# MCU.net
KiCad netlist of a schematic drawn in Altium Designer
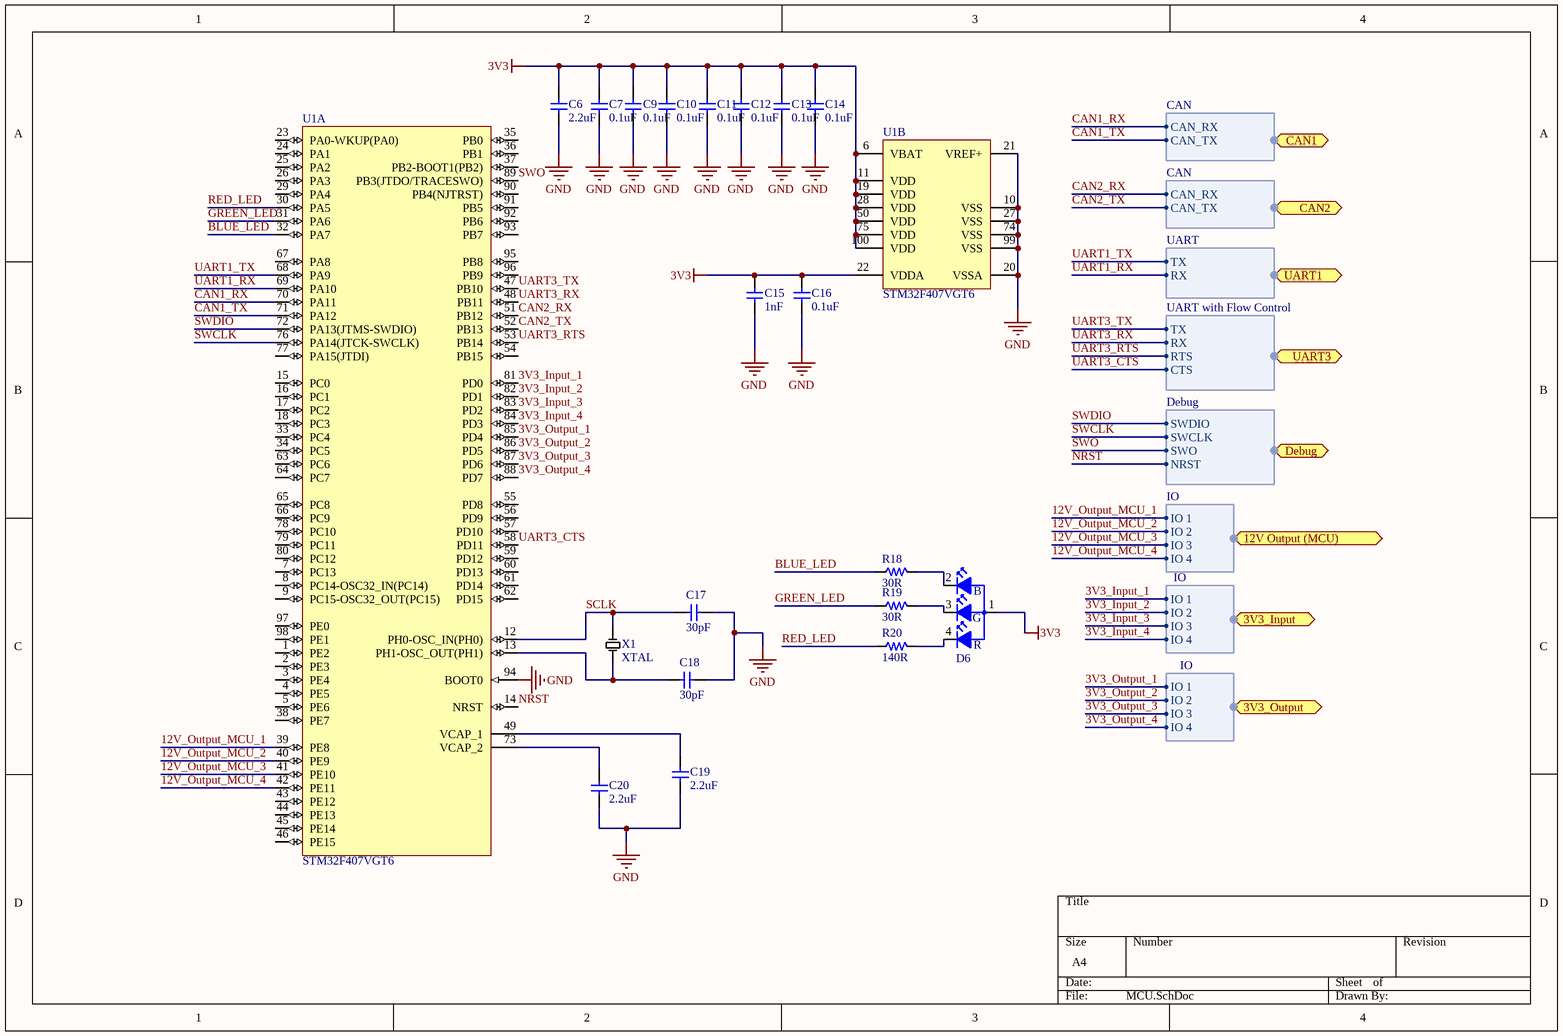
[diagram p0: MCU.SchDoc]

(export (version "E")
  (design (tool "Eeschema 10.0.6"))
  (components
    (comp (ref "C6")
      (value "2.2uF")
      (footprint "PCB_GENERIC_SMD_0603")
      (description "CAP CER 0603 2.2uF 16V X5R 20%")
      (fields (field (name "TOLERANCE") "20%") (field (name "VOLTAGE") "16V"))
      (libsource (lib "CAP-0603") (part "C060-002U2-00"))
    )
    (comp (ref "C7")
      (value "0.1uF")
      (footprint "PCB_GENERIC_SMD_0603")
      (description "CAP CER 0603 0.1uF 16V X5R 20%")
      (fields (field (name "TOLERANCE") "20%") (field (name "VOLTAGE") "16V"))
      (libsource (lib "CAP-0603") (part "C060-000U1-00"))
    )
    (comp (ref "C9")
      (value "0.1uF")
      (footprint "PCB_GENERIC_SMD_0603")
      (description "CAP CER 0603 0.1uF 16V X5R 20%")
      (fields (field (name "TOLERANCE") "20%") (field (name "VOLTAGE") "16V"))
      (libsource (lib "CAP-0603") (part "C060-000U1-00"))
    )
    (comp (ref "C10")
      (value "0.1uF")
      (footprint "PCB_GENERIC_SMD_0603")
      (description "CAP CER 0603 0.1uF 16V X5R 20%")
      (fields (field (name "TOLERANCE") "20%") (field (name "VOLTAGE") "16V"))
      (libsource (lib "CAP-0603") (part "C060-000U1-00"))
    )
    (comp (ref "C11")
      (value "0.1uF")
      (footprint "PCB_GENERIC_SMD_0603")
      (description "CAP CER 0603 0.1uF 16V X5R 20%")
      (fields (field (name "TOLERANCE") "20%") (field (name "VOLTAGE") "16V"))
      (libsource (lib "CAP-0603") (part "C060-000U1-00"))
    )
    (comp (ref "C12")
      (value "0.1uF")
      (footprint "PCB_GENERIC_SMD_0603")
      (description "CAP CER 0603 0.1uF 16V X5R 20%")
      (fields (field (name "TOLERANCE") "20%") (field (name "VOLTAGE") "16V"))
      (libsource (lib "CAP-0603") (part "C060-000U1-00"))
    )
    (comp (ref "C13")
      (value "0.1uF")
      (footprint "PCB_GENERIC_SMD_0603")
      (description "CAP CER 0603 0.1uF 16V X5R 20%")
      (fields (field (name "TOLERANCE") "20%") (field (name "VOLTAGE") "16V"))
      (libsource (lib "CAP-0603") (part "C060-000U1-00"))
    )
    (comp (ref "C14")
      (value "0.1uF")
      (footprint "PCB_GENERIC_SMD_0603")
      (description "CAP CER 0603 0.1uF 16V X5R 20%")
      (fields (field (name "TOLERANCE") "20%") (field (name "VOLTAGE") "16V"))
      (libsource (lib "CAP-0603") (part "C060-000U1-00"))
    )
    (comp (ref "C15")
      (value "1nF")
      (footprint "PCB_GENERIC_SMD_0603")
      (description "CAP CER 0603 1nF 50V X7R 10%")
      (fields (field (name "TOLERANCE") "10%") (field (name "VOLTAGE") "50V"))
      (libsource (lib "CAP-0603") (part "C060-0001N-00"))
    )
    (comp (ref "C16")
      (value "0.1uF")
      (footprint "PCB_GENERIC_SMD_0603")
      (description "CAP CER 0603 0.1uF 16V X5R 20%")
      (fields (field (name "TOLERANCE") "20%") (field (name "VOLTAGE") "16V"))
      (libsource (lib "CAP-0603") (part "C060-000U1-00"))
    )
    (comp (ref "C17")
      (value "30pF")
      (footprint "PCB_GENERIC_SMD_0603")
      (description "CAP CER 0603 30pF 50V NP0 5%")
      (fields (field (name "TOLERANCE") "5%") (field (name "VOLTAGE") "50V"))
      (libsource (lib "CAP-0603") (part "C060-0030P-00"))
    )
    (comp (ref "C18")
      (value "30pF")
      (footprint "PCB_GENERIC_SMD_0603")
      (description "CAP CER 0603 30pF 50V NP0 5%")
      (fields (field (name "TOLERANCE") "5%") (field (name "VOLTAGE") "50V"))
      (libsource (lib "CAP-0603") (part "C060-0030P-00"))
    )
    (comp (ref "C19")
      (value "2.2uF")
      (footprint "PCB_GENERIC_SMD_0603")
      (description "CAP CER 0603 2.2uF 16V X5R 20%")
      (fields (field (name "TOLERANCE") "20%") (field (name "VOLTAGE") "16V"))
      (libsource (lib "CAP-0603") (part "C060-002U2-00"))
    )
    (comp (ref "C20")
      (value "2.2uF")
      (footprint "PCB_GENERIC_SMD_0603")
      (description "CAP CER 0603 2.2uF 16V X5R 20%")
      (fields (field (name "TOLERANCE") "20%") (field (name "VOLTAGE") "16V"))
      (libsource (lib "CAP-0603") (part "C060-002U2-00"))
    )
    (comp (ref "D6")
      (value "D0S4-000CR-00")
      (footprint "CLMVB-FKA")
      (description "LED 4SMD RGB 2Vf 3Vf 3Vf 20mA 10mA 10mA")
      (libsource (lib "LED-4SMD") (part "D0S4-000CR-00"))
    )
    (comp (ref "R18")
      (value "30R")
      (footprint "PCB_GENERIC_SMD_0603")
      (description "RES 0603 30ohm 5% 100mW")
      (fields (field (name "TOLERANCE") "5%") (field (name "POWER") "100mW"))
      (libsource (lib "RES-0603") (part "R060-00300-05"))
    )
    (comp (ref "R19")
      (value "30R")
      (footprint "PCB_GENERIC_SMD_0603")
      (description "RES 0603 30ohm 5% 100mW")
      (fields (field (name "TOLERANCE") "5%") (field (name "POWER") "100mW"))
      (libsource (lib "RES-0603") (part "R060-00300-05"))
    )
    (comp (ref "R20")
      (value "140R")
      (footprint "PCB_GENERIC_SMD_0603")
      (description "RES 0603 140ohm 5% 63mW")
      (fields (field (name "TOLERANCE") "5%") (field (name "POWER") "63mW"))
      (libsource (lib "RES-0603") (part "R060-00141-05"))
    )
    (comp (ref "U1")
      (value "STM32F407VGT6")
      (footprint "STM-LQFP100_M")
      (fields (field (name "MANUFACTURER") "STMicroelectronics"))
      (libsource (lib "STMicroelectronics STM32 F4") (part "STM32F407VGT6"))
    )
    (comp (ref "X1") (value "XTAL") (footprint "CRYSTAL_8MHZ") (libsource (lib "Crystal") (part "Crystal")))
  )
  (nets
    (net (code "8") (name "/3V3_Input_1") (class "Default")
      (node (ref "U1") (pin "81") (pinfunction "PD0_81") (pintype "bidirectional"))
    )
    (net (code "9") (name "/3V3_Input_2") (class "Default")
      (node (ref "U1") (pin "82") (pinfunction "PD1_82") (pintype "bidirectional"))
    )
    (net (code "10") (name "/3V3_Input_3") (class "Default")
      (node (ref "U1") (pin "83") (pinfunction "PD2_83") (pintype "bidirectional"))
    )
    (net (code "11") (name "/3V3_Input_4") (class "Default")
      (node (ref "U1") (pin "84") (pinfunction "PD3_84") (pintype "bidirectional"))
    )
    (net (code "12") (name "/3V3_Output_1") (class "Default")
      (node (ref "U1") (pin "85") (pinfunction "PD4_85") (pintype "bidirectional"))
    )
    (net (code "13") (name "/3V3_Output_2") (class "Default")
      (node (ref "U1") (pin "86") (pinfunction "PD5_86") (pintype "bidirectional"))
    )
    (net (code "14") (name "/3V3_Output_3") (class "Default")
      (node (ref "U1") (pin "87") (pinfunction "PD6_87") (pintype "bidirectional"))
    )
    (net (code "15") (name "/3V3_Output_4") (class "Default")
      (node (ref "U1") (pin "88") (pinfunction "PD7_88") (pintype "bidirectional"))
    )
    (net (code "16") (name "/12V_Output_MCU_1") (class "Default")
      (node (ref "U1") (pin "39") (pinfunction "PE8_39") (pintype "bidirectional"))
    )
    (net (code "17") (name "/12V_Output_MCU_2") (class "Default")
      (node (ref "U1") (pin "40") (pinfunction "PE9_40") (pintype "bidirectional"))
    )
    (net (code "18") (name "/12V_Output_MCU_3") (class "Default")
      (node (ref "U1") (pin "41") (pinfunction "PE10_41") (pintype "bidirectional"))
    )
    (net (code "19") (name "/12V_Output_MCU_4") (class "Default")
      (node (ref "U1") (pin "42") (pinfunction "PE11_42") (pintype "bidirectional"))
    )
    (net (code "20") (name "/BLUE_LED") (class "Default")
      (node (ref "R18") (pin "1") (pinfunction "1_1") (pintype "passive"))
      (node (ref "U1") (pin "32") (pinfunction "PA7_32") (pintype "bidirectional"))
    )
    (net (code "21") (name "/CAN1_RX") (class "Default")
      (node (ref "U1") (pin "70") (pinfunction "PA11_70") (pintype "bidirectional"))
    )
    (net (code "22") (name "/CAN1_TX") (class "Default")
      (node (ref "U1") (pin "71") (pinfunction "PA12_71") (pintype "bidirectional"))
    )
    (net (code "23") (name "/CAN2_RX") (class "Default")
      (node (ref "U1") (pin "51") (pinfunction "PB12_51") (pintype "bidirectional"))
    )
    (net (code "24") (name "/CAN2_TX") (class "Default")
      (node (ref "U1") (pin "52") (pinfunction "PB13_52") (pintype "bidirectional"))
    )
    (net (code "25") (name "/GREEN_LED") (class "Default")
      (node (ref "R19") (pin "1") (pinfunction "1_1") (pintype "passive"))
      (node (ref "U1") (pin "31") (pinfunction "PA6_31") (pintype "bidirectional"))
    )
    (net (code "26") (name "/NRST") (class "Default")
      (node (ref "U1") (pin "14") (pinfunction "NRST_14") (pintype "bidirectional"))
    )
    (net (code "27") (name "/RED_LED") (class "Default")
      (node (ref "R20") (pin "1") (pinfunction "1_1") (pintype "passive"))
      (node (ref "U1") (pin "30") (pinfunction "PA5_30") (pintype "bidirectional"))
    )
    (net (code "28") (name "/SCLK") (class "Default")
      (node (ref "C17") (pin "2") (pinfunction "2_2") (pintype "passive"))
      (node (ref "U1") (pin "12") (pinfunction "PH0-OSC_IN(PH0)_12") (pintype "bidirectional"))
      (node (ref "X1") (pin "1") (pintype "passive"))
    )
    (net (code "29") (name "/SWCLK") (class "Default")
      (node (ref "U1") (pin "76") (pinfunction "PA14(JTCK-SWCLK)_76") (pintype "bidirectional"))
    )
    (net (code "30") (name "/SWDIO") (class "Default")
      (node (ref "U1") (pin "72") (pinfunction "PA13(JTMS-SWDIO)_72") (pintype "bidirectional"))
    )
    (net (code "31") (name "/SWO") (class "Default")
      (node (ref "U1") (pin "89") (pinfunction "PB3(JTDO/TRACESWO)_89") (pintype "bidirectional"))
    )
    (net (code "32") (name "/UART1_RX") (class "Default")
      (node (ref "U1") (pin "69") (pinfunction "PA10_69") (pintype "bidirectional"))
    )
    (net (code "33") (name "/UART1_TX") (class "Default")
      (node (ref "U1") (pin "68") (pinfunction "PA9_68") (pintype "bidirectional"))
    )
    (net (code "34") (name "/UART3_CTS") (class "Default")
      (node (ref "U1") (pin "58") (pinfunction "PD11_58") (pintype "bidirectional"))
    )
    (net (code "35") (name "/UART3_RTS") (class "Default")
      (node (ref "U1") (pin "53") (pinfunction "PB14_53") (pintype "bidirectional"))
    )
    (net (code "36") (name "/UART3_RX") (class "Default")
      (node (ref "U1") (pin "48") (pinfunction "PB11_48") (pintype "bidirectional"))
    )
    (net (code "37") (name "/UART3_TX") (class "Default")
      (node (ref "U1") (pin "47") (pinfunction "PB10_47") (pintype "bidirectional"))
    )
    (net (code "43") (name "3V3") (class "Default")
      (node (ref "C10") (pin "2") (pinfunction "2_2") (pintype "passive"))
      (node (ref "C11") (pin "2") (pinfunction "2_2") (pintype "passive"))
      (node (ref "C12") (pin "2") (pinfunction "2_2") (pintype "passive"))
      (node (ref "C13") (pin "2") (pinfunction "2_2") (pintype "passive"))
      (node (ref "C14") (pin "2") (pinfunction "2_2") (pintype "passive"))
      (node (ref "C15") (pin "2") (pinfunction "2_2") (pintype "passive"))
      (node (ref "C16") (pin "2") (pinfunction "2_2") (pintype "passive"))
      (node (ref "C6") (pin "2") (pinfunction "2_2") (pintype "passive"))
      (node (ref "C7") (pin "2") (pinfunction "2_2") (pintype "passive"))
      (node (ref "C9") (pin "2") (pinfunction "2_2") (pintype "passive"))
      (node (ref "D6") (pin "1") (pinfunction "Red_1") (pintype "passive"))
      (node (ref "U1") (pin "100") (pinfunction "VDD_100") (pintype "power_in"))
      (node (ref "U1") (pin "11") (pinfunction "VDD_11") (pintype "power_in"))
      (node (ref "U1") (pin "19") (pinfunction "VDD_19") (pintype "power_in"))
      (node (ref "U1") (pin "22") (pinfunction "VDDA_22") (pintype "power_in"))
      (node (ref "U1") (pin "28") (pinfunction "VDD_28") (pintype "power_in"))
      (node (ref "U1") (pin "50") (pinfunction "VDD_50") (pintype "power_in"))
      (node (ref "U1") (pin "6") (pinfunction "VBAT_6") (pintype "power_in"))
      (node (ref "U1") (pin "75") (pinfunction "VDD_75") (pintype "power_in"))
    )
    (net (code "44") (name "GND") (class "Default")
      (node (ref "C10") (pin "1") (pinfunction "1_1") (pintype "passive"))
      (node (ref "C11") (pin "1") (pinfunction "1_1") (pintype "passive"))
      (node (ref "C12") (pin "1") (pinfunction "1_1") (pintype "passive"))
      (node (ref "C13") (pin "1") (pinfunction "1_1") (pintype "passive"))
      (node (ref "C14") (pin "1") (pinfunction "1_1") (pintype "passive"))
      (node (ref "C15") (pin "1") (pinfunction "1_1") (pintype "passive"))
      (node (ref "C16") (pin "1") (pinfunction "1_1") (pintype "passive"))
      (node (ref "C17") (pin "1") (pinfunction "1_1") (pintype "passive"))
      (node (ref "C18") (pin "1") (pinfunction "1_1") (pintype "passive"))
      (node (ref "C19") (pin "1") (pinfunction "1_1") (pintype "passive"))
      (node (ref "C20") (pin "1") (pinfunction "1_1") (pintype "passive"))
      (node (ref "C6") (pin "1") (pinfunction "1_1") (pintype "passive"))
      (node (ref "C7") (pin "1") (pinfunction "1_1") (pintype "passive"))
      (node (ref "C9") (pin "1") (pinfunction "1_1") (pintype "passive"))
      (node (ref "U1") (pin "10") (pinfunction "VSS_10") (pintype "power_in"))
      (node (ref "U1") (pin "20") (pinfunction "VSSA_20") (pintype "power_in"))
      (node (ref "U1") (pin "21") (pinfunction "VREF+_21") (pintype "power_in"))
      (node (ref "U1") (pin "27") (pinfunction "VSS_27") (pintype "power_in"))
      (node (ref "U1") (pin "74") (pinfunction "VSS_74") (pintype "power_in"))
      (node (ref "U1") (pin "94") (pinfunction "BOOT0_94") (pintype "input"))
      (node (ref "U1") (pin "99") (pinfunction "VSS_99") (pintype "power_in"))
    )
    (net (code "45") (name "Net-(D6-Blue)") (class "Default")
      (node (ref "D6") (pin "3") (pinfunction "Blue_3") (pintype "passive"))
      (node (ref "R19") (pin "2") (pinfunction "2_2") (pintype "passive"))
    )
    (net (code "46") (name "Net-(D6-Green)") (class "Default")
      (node (ref "D6") (pin "2") (pinfunction "Green_2") (pintype "passive"))
      (node (ref "R18") (pin "2") (pinfunction "2_2") (pintype "passive"))
    )
    (net (code "47") (name "Net-(D6-Pad4)") (class "Default")
      (node (ref "D6") (pin "4") (pinfunction "4_4") (pintype "passive"))
      (node (ref "R20") (pin "2") (pinfunction "2_2") (pintype "passive"))
    )
    (net (code "48") (name "Net-(U1A-PH1-OSC_OUT(PH1))") (class "Default")
      (node (ref "C18") (pin "2") (pinfunction "2_2") (pintype "passive"))
      (node (ref "U1") (pin "13") (pinfunction "PH1-OSC_OUT(PH1)_13") (pintype "bidirectional"))
      (node (ref "X1") (pin "2") (pintype "passive"))
    )
    (net (code "49") (name "Net-(U1A-VCAP_1)") (class "Default")
      (node (ref "C19") (pin "2") (pinfunction "2_2") (pintype "passive"))
      (node (ref "U1") (pin "49") (pinfunction "VCAP_1_49") (pintype "power_in"))
    )
    (net (code "50") (name "Net-(U1A-VCAP_2)") (class "Default")
      (node (ref "C20") (pin "2") (pinfunction "2_2") (pintype "passive"))
      (node (ref "U1") (pin "73") (pinfunction "VCAP_2_73") (pintype "power_in"))
    )
    (net (code "51") (name "unconnected-(U1A-PA0-WKUP(PA0)-Pad23)") (class "Default")
      (node (ref "U1") (pin "23") (pinfunction "PA0-WKUP(PA0)_23") (pintype "bidirectional"))
    )
    (net (code "52") (name "unconnected-(U1A-PA1-Pad24)") (class "Default")
      (node (ref "U1") (pin "24") (pinfunction "PA1_24") (pintype "bidirectional"))
    )
    (net (code "53") (name "unconnected-(U1A-PA2-Pad25)") (class "Default")
      (node (ref "U1") (pin "25") (pinfunction "PA2_25") (pintype "bidirectional"))
    )
    (net (code "54") (name "unconnected-(U1A-PA3-Pad26)") (class "Default")
      (node (ref "U1") (pin "26") (pinfunction "PA3_26") (pintype "bidirectional"))
    )
    (net (code "55") (name "unconnected-(U1A-PA4-Pad29)") (class "Default")
      (node (ref "U1") (pin "29") (pinfunction "PA4_29") (pintype "bidirectional"))
    )
    (net (code "56") (name "unconnected-(U1A-PA8-Pad67)") (class "Default")
      (node (ref "U1") (pin "67") (pinfunction "PA8_67") (pintype "bidirectional"))
    )
    (net (code "57") (name "unconnected-(U1A-PA15(JTDI)-Pad77)") (class "Default")
      (node (ref "U1") (pin "77") (pinfunction "PA15(JTDI)_77") (pintype "bidirectional"))
    )
    (net (code "58") (name "unconnected-(U1A-PB0-Pad35)") (class "Default")
      (node (ref "U1") (pin "35") (pinfunction "PB0_35") (pintype "bidirectional"))
    )
    (net (code "59") (name "unconnected-(U1A-PB1-Pad36)") (class "Default")
      (node (ref "U1") (pin "36") (pinfunction "PB1_36") (pintype "bidirectional"))
    )
    (net (code "60") (name "unconnected-(U1A-PB2-BOOT1(PB2)-Pad37)") (class "Default")
      (node (ref "U1") (pin "37") (pinfunction "PB2-BOOT1(PB2)_37") (pintype "bidirectional"))
    )
    (net (code "61") (name "unconnected-(U1A-PB4(NJTRST)-Pad90)") (class "Default")
      (node (ref "U1") (pin "90") (pinfunction "PB4(NJTRST)_90") (pintype "bidirectional"))
    )
    (net (code "62") (name "unconnected-(U1A-PB5-Pad91)") (class "Default")
      (node (ref "U1") (pin "91") (pinfunction "PB5_91") (pintype "bidirectional"))
    )
    (net (code "63") (name "unconnected-(U1A-PB6-Pad92)") (class "Default")
      (node (ref "U1") (pin "92") (pinfunction "PB6_92") (pintype "bidirectional"))
    )
    (net (code "64") (name "unconnected-(U1A-PB7-Pad93)") (class "Default")
      (node (ref "U1") (pin "93") (pinfunction "PB7_93") (pintype "bidirectional"))
    )
    (net (code "65") (name "unconnected-(U1A-PB8-Pad95)") (class "Default")
      (node (ref "U1") (pin "95") (pinfunction "PB8_95") (pintype "bidirectional"))
    )
    (net (code "66") (name "unconnected-(U1A-PB9-Pad96)") (class "Default")
      (node (ref "U1") (pin "96") (pinfunction "PB9_96") (pintype "bidirectional"))
    )
    (net (code "67") (name "unconnected-(U1A-PB15-Pad54)") (class "Default")
      (node (ref "U1") (pin "54") (pinfunction "PB15_54") (pintype "bidirectional"))
    )
    (net (code "68") (name "unconnected-(U1A-PC0-Pad15)") (class "Default")
      (node (ref "U1") (pin "15") (pinfunction "PC0_15") (pintype "bidirectional"))
    )
    (net (code "69") (name "unconnected-(U1A-PC1-Pad16)") (class "Default")
      (node (ref "U1") (pin "16") (pinfunction "PC1_16") (pintype "bidirectional"))
    )
    (net (code "70") (name "unconnected-(U1A-PC2-Pad17)") (class "Default")
      (node (ref "U1") (pin "17") (pinfunction "PC2_17") (pintype "bidirectional"))
    )
    (net (code "71") (name "unconnected-(U1A-PC3-Pad18)") (class "Default")
      (node (ref "U1") (pin "18") (pinfunction "PC3_18") (pintype "bidirectional"))
    )
    (net (code "72") (name "unconnected-(U1A-PC4-Pad33)") (class "Default")
      (node (ref "U1") (pin "33") (pinfunction "PC4_33") (pintype "bidirectional"))
    )
    (net (code "73") (name "unconnected-(U1A-PC5-Pad34)") (class "Default")
      (node (ref "U1") (pin "34") (pinfunction "PC5_34") (pintype "bidirectional"))
    )
    (net (code "74") (name "unconnected-(U1A-PC6-Pad63)") (class "Default")
      (node (ref "U1") (pin "63") (pinfunction "PC6_63") (pintype "bidirectional"))
    )
    (net (code "75") (name "unconnected-(U1A-PC7-Pad64)") (class "Default")
      (node (ref "U1") (pin "64") (pinfunction "PC7_64") (pintype "bidirectional"))
    )
    (net (code "76") (name "unconnected-(U1A-PC8-Pad65)") (class "Default")
      (node (ref "U1") (pin "65") (pinfunction "PC8_65") (pintype "bidirectional"))
    )
    (net (code "77") (name "unconnected-(U1A-PC9-Pad66)") (class "Default")
      (node (ref "U1") (pin "66") (pinfunction "PC9_66") (pintype "bidirectional"))
    )
    (net (code "78") (name "unconnected-(U1A-PC10-Pad78)") (class "Default")
      (node (ref "U1") (pin "78") (pinfunction "PC10_78") (pintype "bidirectional"))
    )
    (net (code "79") (name "unconnected-(U1A-PC11-Pad79)") (class "Default")
      (node (ref "U1") (pin "79") (pinfunction "PC11_79") (pintype "bidirectional"))
    )
    (net (code "80") (name "unconnected-(U1A-PC12-Pad80)") (class "Default")
      (node (ref "U1") (pin "80") (pinfunction "PC12_80") (pintype "bidirectional"))
    )
    (net (code "81") (name "unconnected-(U1A-PC13-Pad7)") (class "Default")
      (node (ref "U1") (pin "7") (pinfunction "PC13_7") (pintype "bidirectional"))
    )
    (net (code "82") (name "unconnected-(U1A-PC14-OSC32_IN(PC14)-Pad8)") (class "Default")
      (node (ref "U1") (pin "8") (pinfunction "PC14-OSC32_IN(PC14)_8") (pintype "bidirectional"))
    )
    (net (code "83") (name "unconnected-(U1A-PC15-OSC32_OUT(PC15)-Pad9)") (class "Default")
      (node (ref "U1") (pin "9") (pinfunction "PC15-OSC32_OUT(PC15)_9") (pintype "bidirectional"))
    )
    (net (code "84") (name "unconnected-(U1A-PD8-Pad55)") (class "Default")
      (node (ref "U1") (pin "55") (pinfunction "PD8_55") (pintype "bidirectional"))
    )
    (net (code "85") (name "unconnected-(U1A-PD9-Pad56)") (class "Default")
      (node (ref "U1") (pin "56") (pinfunction "PD9_56") (pintype "bidirectional"))
    )
    (net (code "86") (name "unconnected-(U1A-PD10-Pad57)") (class "Default")
      (node (ref "U1") (pin "57") (pinfunction "PD10_57") (pintype "bidirectional"))
    )
    (net (code "87") (name "unconnected-(U1A-PD12-Pad59)") (class "Default")
      (node (ref "U1") (pin "59") (pinfunction "PD12_59") (pintype "bidirectional"))
    )
    (net (code "88") (name "unconnected-(U1A-PD13-Pad60)") (class "Default")
      (node (ref "U1") (pin "60") (pinfunction "PD13_60") (pintype "bidirectional"))
    )
    (net (code "89") (name "unconnected-(U1A-PD14-Pad61)") (class "Default")
      (node (ref "U1") (pin "61") (pinfunction "PD14_61") (pintype "bidirectional"))
    )
    (net (code "90") (name "unconnected-(U1A-PD15-Pad62)") (class "Default")
      (node (ref "U1") (pin "62") (pinfunction "PD15_62") (pintype "bidirectional"))
    )
    (net (code "91") (name "unconnected-(U1A-PE0-Pad97)") (class "Default")
      (node (ref "U1") (pin "97") (pinfunction "PE0_97") (pintype "bidirectional"))
    )
    (net (code "92") (name "unconnected-(U1A-PE1-Pad98)") (class "Default")
      (node (ref "U1") (pin "98") (pinfunction "PE1_98") (pintype "bidirectional"))
    )
    (net (code "93") (name "unconnected-(U1A-PE2-Pad1)") (class "Default")
      (node (ref "U1") (pin "1") (pinfunction "PE2_1") (pintype "bidirectional"))
    )
    (net (code "94") (name "unconnected-(U1A-PE3-Pad2)") (class "Default")
      (node (ref "U1") (pin "2") (pinfunction "PE3_2") (pintype "bidirectional"))
    )
    (net (code "95") (name "unconnected-(U1A-PE4-Pad3)") (class "Default")
      (node (ref "U1") (pin "3") (pinfunction "PE4_3") (pintype "bidirectional"))
    )
    (net (code "96") (name "unconnected-(U1A-PE5-Pad4)") (class "Default")
      (node (ref "U1") (pin "4") (pinfunction "PE5_4") (pintype "bidirectional"))
    )
    (net (code "97") (name "unconnected-(U1A-PE6-Pad5)") (class "Default")
      (node (ref "U1") (pin "5") (pinfunction "PE6_5") (pintype "bidirectional"))
    )
    (net (code "98") (name "unconnected-(U1A-PE7-Pad38)") (class "Default")
      (node (ref "U1") (pin "38") (pinfunction "PE7_38") (pintype "bidirectional"))
    )
    (net (code "99") (name "unconnected-(U1A-PE12-Pad43)") (class "Default")
      (node (ref "U1") (pin "43") (pinfunction "PE12_43") (pintype "bidirectional"))
    )
    (net (code "100") (name "unconnected-(U1A-PE13-Pad44)") (class "Default")
      (node (ref "U1") (pin "44") (pinfunction "PE13_44") (pintype "bidirectional"))
    )
    (net (code "101") (name "unconnected-(U1A-PE14-Pad45)") (class "Default")
      (node (ref "U1") (pin "45") (pinfunction "PE14_45") (pintype "bidirectional"))
    )
    (net (code "102") (name "unconnected-(U1A-PE15-Pad46)") (class "Default")
      (node (ref "U1") (pin "46") (pinfunction "PE15_46") (pintype "bidirectional"))
    )
  )
)
